# mano_rev_1_2_b.net
KiCad netlist of a schematic drawn in EAGLE
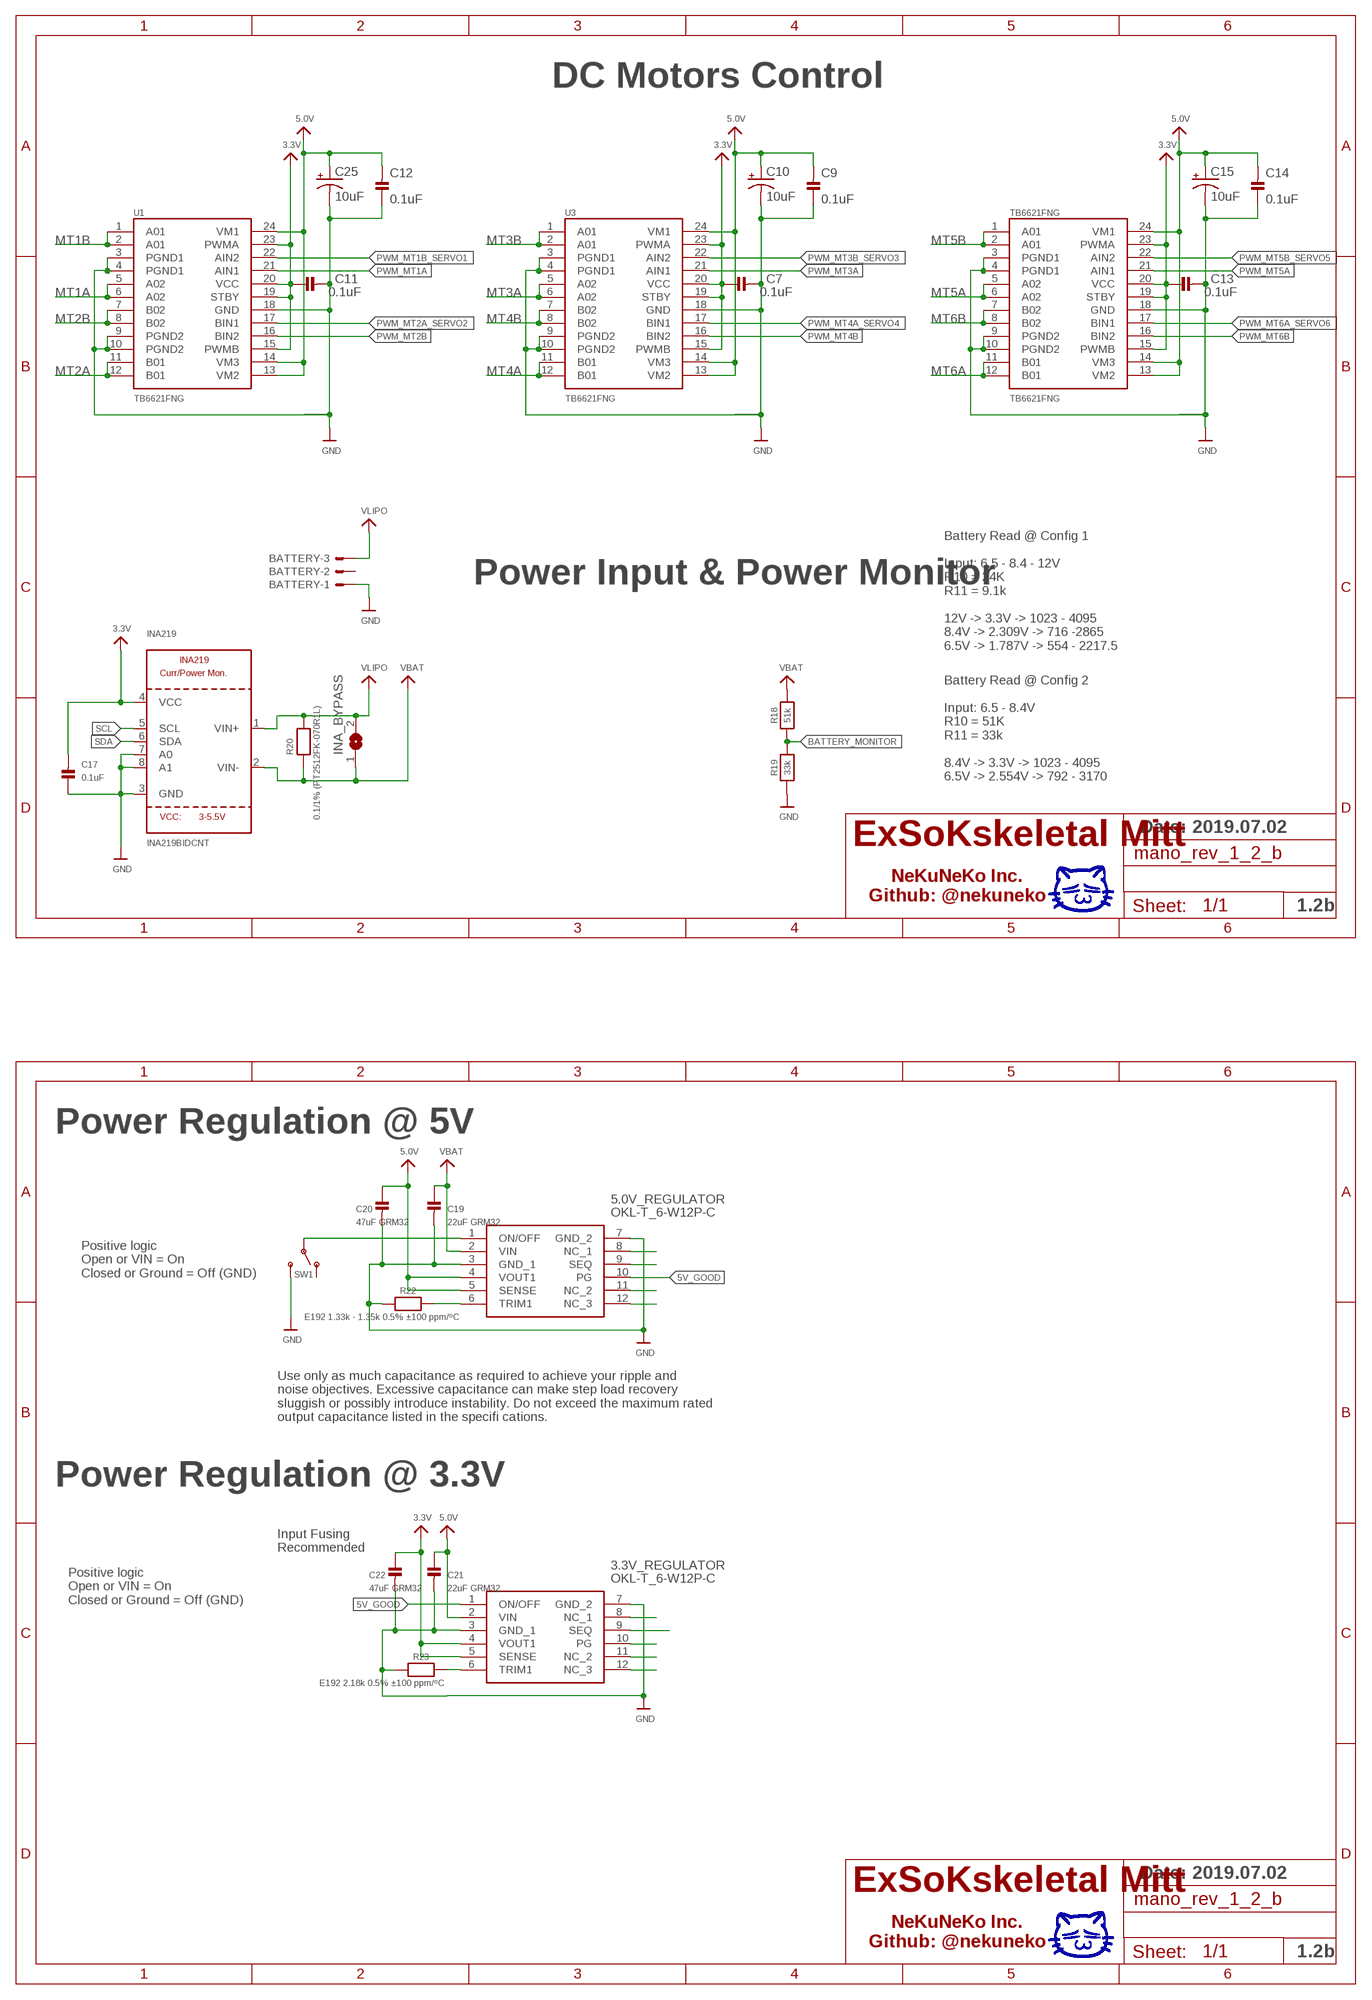
[diagram p0: schematic, sheet 1, part 1 of 2]
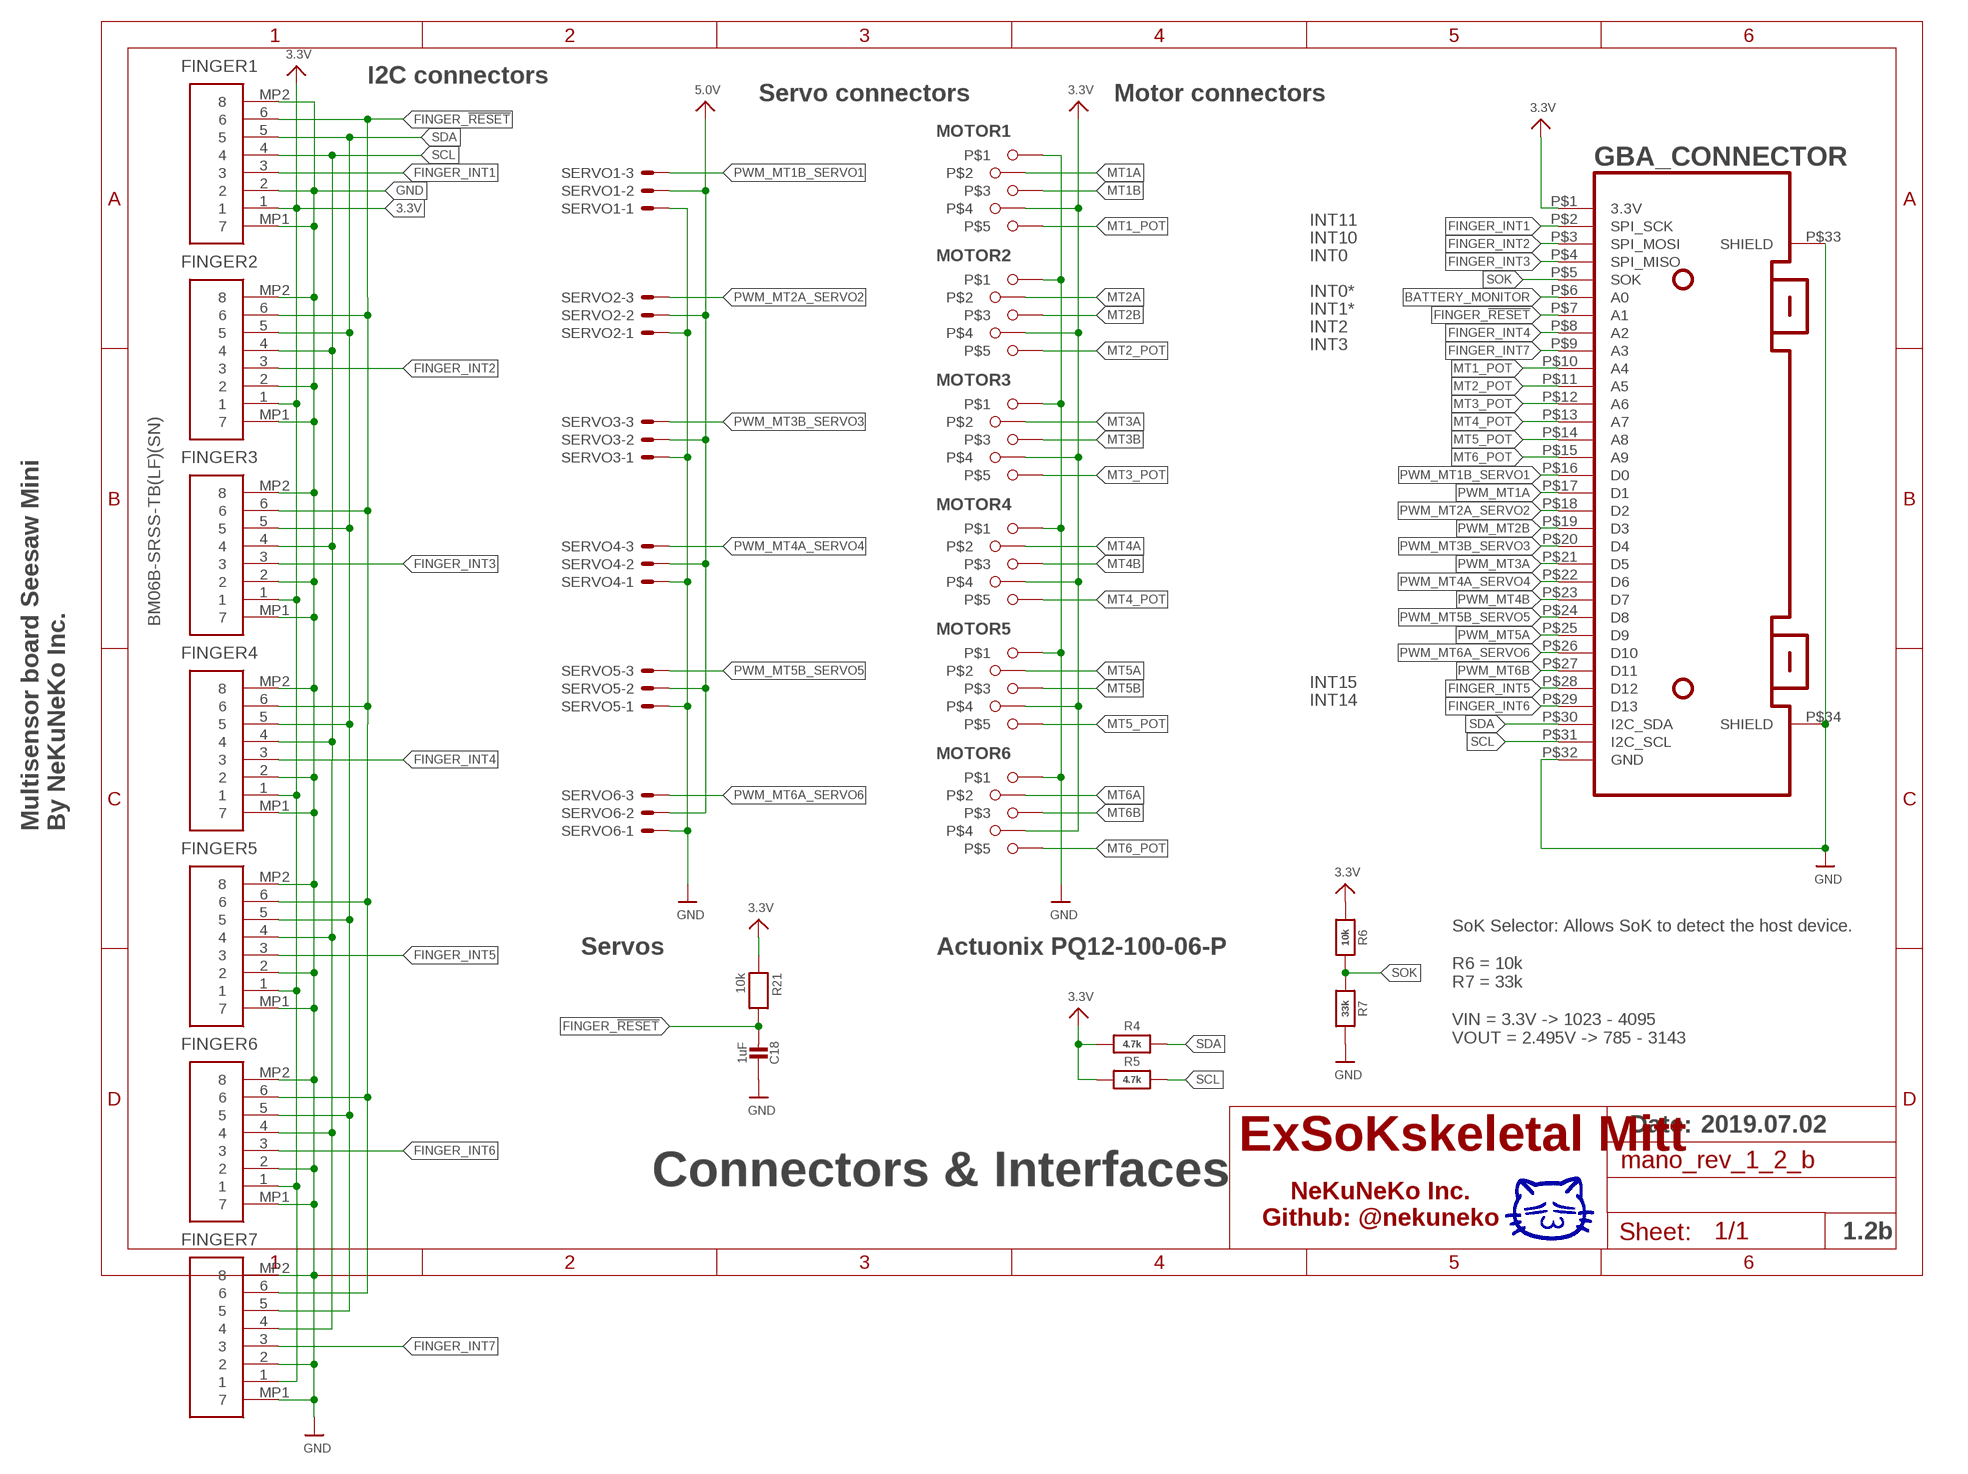
[diagram p1: schematic, sheet 1, part 2 of 2]

(export (version "E")
  (design (tool "Eeschema 10.0.6"))
  (components
    (comp (ref "3.3V_REGULATOR")
      (value "OKL-T_6-W12P-C")
      (footprint "eagle-import:OKL-T3-W12")
      (fields
        (field (name "MANUFACTURER_PART_NUMBER") "OKL-T/6-W12P-C")
        (field (name "MOUSER_PART_NUMBER") "580-OKL-T/6-W12P-C")
      )
      (libsource (lib "eagle-import") (part "OKL-T_6-W12P-C"))
    )
    (comp (ref "5.0V_REGULATOR")
      (value "OKL-T_6-W12P-C")
      (footprint "eagle-import:OKL-T3-W12")
      (fields
        (field (name "MANUFACTURER_PART_NUMBER") "OKL-T/6-W12P-C")
        (field (name "MOUSER_PART_NUMBER") "580-OKL-T/6-W12P-C")
      )
      (libsource (lib "eagle-import") (part "OKL-T_6-W12P-C"))
    )
    (comp (ref "BATTERY")
      (value "JST-XH-03-PIN-LONG-PAD")
      (footprint "eagle-import:JST-XH-03-PACKAGE-LONG-PAD")
      (libsource (lib "eagle-import") (part "JST-XH-03-PIN-LONG-PAD"))
    )
    (comp (ref "C7")
      (value "0.1uF")
      (footprint "eagle-import:_0603")
      (libsource (lib "eagle-import") (part "microbuilder_CAP_CERAMIC_0603"))
    )
    (comp (ref "C9")
      (value "0.1uF")
      (footprint "eagle-import:_0603")
      (libsource (lib "eagle-import") (part "microbuilder_CAP_CERAMIC_0603"))
    )
    (comp (ref "C10")
      (value "10uF")
      (footprint "eagle-import:0603-POLAR")
      (fields (field (name "MPN") "F981A106MMA"))
      (libsource (lib "eagle-import") (part "10UF-POLAR-0603-6.3V-20%(TANT)"))
    )
    (comp (ref "C11")
      (value "0.1uF")
      (footprint "eagle-import:_0603")
      (libsource (lib "eagle-import") (part "microbuilder_CAP_CERAMIC_0603"))
    )
    (comp (ref "C12")
      (value "0.1uF")
      (footprint "eagle-import:_0603")
      (libsource (lib "eagle-import") (part "microbuilder_CAP_CERAMIC_0603"))
    )
    (comp (ref "C13")
      (value "0.1uF")
      (footprint "eagle-import:_0603")
      (libsource (lib "eagle-import") (part "microbuilder_CAP_CERAMIC_0603"))
    )
    (comp (ref "C14")
      (value "0.1uF")
      (footprint "eagle-import:_0603")
      (libsource (lib "eagle-import") (part "microbuilder_CAP_CERAMIC_0603"))
    )
    (comp (ref "C15")
      (value "10uF")
      (footprint "eagle-import:0603-POLAR")
      (fields (field (name "MPN") "F981A106MMA"))
      (libsource (lib "eagle-import") (part "10UF-POLAR-0603-6.3V-20%(TANT)"))
    )
    (comp (ref "C17")
      (value "0.1uF")
      (footprint "eagle-import:_0603")
      (libsource (lib "eagle-import") (part "microbuilder_CAP_CERAMIC_0603"))
    )
    (comp (ref "C18")
      (value "1uF")
      (footprint "eagle-import:MICROBUILDER__0603")
      (libsource (lib "eagle-import") (part "CAP_CERAMIC_0603"))
    )
    (comp (ref "C19")
      (value "22uF GRM32")
      (footprint "eagle-import:1206")
      (libsource (lib "eagle-import") (part "CAP_CERAMIC1206"))
    )
    (comp (ref "C20")
      (value "47uF GRM32")
      (footprint "eagle-import:1206")
      (libsource (lib "eagle-import") (part "CAP_CERAMIC1206"))
    )
    (comp (ref "C21")
      (value "22uF GRM32")
      (footprint "eagle-import:1206")
      (libsource (lib "eagle-import") (part "CAP_CERAMIC1206"))
    )
    (comp (ref "C22")
      (value "47uF GRM32")
      (footprint "eagle-import:1206")
      (libsource (lib "eagle-import") (part "CAP_CERAMIC1206"))
    )
    (comp (ref "C25")
      (value "10uF")
      (footprint "eagle-import:0603-POLAR")
      (fields (field (name "MPN") "F981A106MMA"))
      (libsource (lib "eagle-import") (part "10UF-POLAR-0603-6.3V-20%(TANT)"))
    )
    (comp (ref "FINGER1")
      (value "BM06B-SRSS-TB(LF)(SN)")
      (footprint "eagle-import:BM06BSRSSTBLFSN")
      (fields (field (name "RS_PART_NUMBER") "5468782"))
      (libsource (lib "eagle-import") (part "BM06B-SRSS-TB(LF)(SN)"))
    )
    (comp (ref "FINGER2")
      (value "BM06B-SRSS-TB(LF)(SN)")
      (footprint "eagle-import:BM06BSRSSTBLFSN")
      (fields (field (name "RS_PART_NUMBER") "5468782"))
      (libsource (lib "eagle-import") (part "BM06B-SRSS-TB(LF)(SN)"))
    )
    (comp (ref "FINGER3")
      (value "BM06B-SRSS-TB(LF)(SN)")
      (footprint "eagle-import:BM06BSRSSTBLFSN")
      (fields (field (name "RS_PART_NUMBER") "5468782"))
      (libsource (lib "eagle-import") (part "BM06B-SRSS-TB(LF)(SN)"))
    )
    (comp (ref "FINGER4")
      (value "BM06B-SRSS-TB(LF)(SN)")
      (footprint "eagle-import:BM06BSRSSTBLFSN")
      (fields (field (name "RS_PART_NUMBER") "5468782"))
      (libsource (lib "eagle-import") (part "BM06B-SRSS-TB(LF)(SN)"))
    )
    (comp (ref "FINGER5")
      (value "BM06B-SRSS-TB(LF)(SN)")
      (footprint "eagle-import:BM06BSRSSTBLFSN")
      (fields (field (name "RS_PART_NUMBER") "5468782"))
      (libsource (lib "eagle-import") (part "BM06B-SRSS-TB(LF)(SN)"))
    )
    (comp (ref "FINGER6")
      (value "BM06B-SRSS-TB(LF)(SN)")
      (footprint "eagle-import:BM06BSRSSTBLFSN")
      (fields (field (name "RS_PART_NUMBER") "5468782"))
      (libsource (lib "eagle-import") (part "BM06B-SRSS-TB(LF)(SN)"))
    )
    (comp (ref "FINGER7")
      (value "BM06B-SRSS-TB(LF)(SN)")
      (footprint "eagle-import:BM06BSRSSTBLFSN")
      (fields (field (name "RS_PART_NUMBER") "5468782"))
      (libsource (lib "eagle-import") (part "BM06B-SRSS-TB(LF)(SN)"))
    )
    (comp (ref "GBA_CONNECTOR")
      (value "GBA_CARTRIDGEGBA_CARTRIDGE2")
      (footprint "eagle-import:GBA_CARTRIDGE2")
      (libsource (lib "eagle-import") (part "GBA_CARTRIDGEGBA_CARTRIDGE2"))
    )
    (comp (ref "INA219")
      (value "INA219BIDCNT")
      (footprint "eagle-import:SOT23-8")
      (libsource (lib "eagle-import") (part "INA219"))
    )
    (comp (ref "INA_BYPASS")
      (value "SOLDERJUMPERREFLOW_NOPASTE")
      (footprint "eagle-import:SOLDERJUMPER_REFLOW_NOPASTE")
      (libsource (lib "eagle-import") (part "SOLDERJUMPERREFLOW_NOPASTE"))
    )
    (comp (ref "MOTOR1")
      (value "Actuonix PQ12-100-06-P")
      (footprint "eagle-import:5PIN")
      (libsource (lib "eagle-import") (part "5PIN"))
    )
    (comp (ref "MOTOR2")
      (value "Actuonix PQ12-100-06-P")
      (footprint "eagle-import:5PIN")
      (libsource (lib "eagle-import") (part "5PIN"))
    )
    (comp (ref "MOTOR3")
      (value "Actuonix PQ12-100-06-P")
      (footprint "eagle-import:5PIN")
      (libsource (lib "eagle-import") (part "5PIN"))
    )
    (comp (ref "MOTOR4")
      (value "Actuonix PQ12-100-06-P")
      (footprint "eagle-import:5PIN")
      (libsource (lib "eagle-import") (part "5PIN"))
    )
    (comp (ref "MOTOR5")
      (value "Actuonix PQ12-100-06-P")
      (footprint "eagle-import:5PIN")
      (libsource (lib "eagle-import") (part "5PIN"))
    )
    (comp (ref "MOTOR6")
      (value "Actuonix PQ12-100-06-P")
      (footprint "eagle-import:5PIN")
      (libsource (lib "eagle-import") (part "5PIN"))
    )
    (comp (ref "R4")
      (value "4.7k")
      (footprint "eagle-import:_0603")
      (libsource (lib "eagle-import") (part "RESISTOR_0603"))
    )
    (comp (ref "R5")
      (value "4.7k")
      (footprint "eagle-import:_0603")
      (libsource (lib "eagle-import") (part "RESISTOR_0603"))
    )
    (comp (ref "R6")
      (value "10k")
      (footprint "eagle-import:_0603")
      (libsource (lib "eagle-import") (part "RESISTOR_0603"))
    )
    (comp (ref "R7")
      (value "33k")
      (footprint "eagle-import:_0603")
      (libsource (lib "eagle-import") (part "RESISTOR_0603"))
    )
    (comp (ref "R18")
      (value "51k")
      (footprint "eagle-import:_0603")
      (libsource (lib "eagle-import") (part "RESISTOR_0603"))
    )
    (comp (ref "R19")
      (value "33k")
      (footprint "eagle-import:_0603")
      (libsource (lib "eagle-import") (part "RESISTOR_0603"))
    )
    (comp (ref "R20")
      (value "0.1/1% (PT2512FK-070R1L)")
      (footprint "eagle-import:2512")
      (libsource (lib "eagle-import") (part "RESISTOR2512"))
    )
    (comp (ref "R21")
      (value "10k")
      (footprint "eagle-import:_0603")
      (libsource (lib "eagle-import") (part "RESISTOR_0603"))
    )
    (comp (ref "R22")
      (value "E192 1.33k - 1.35k 0.5% ±100 ppm/ºC")
      (footprint "eagle-import:_0603")
      (libsource (lib "eagle-import") (part "RESISTOR_0603"))
    )
    (comp (ref "R23")
      (value "E192 2.18k 0.5% ±100 ppm/ºC")
      (footprint "eagle-import:_0603")
      (libsource (lib "eagle-import") (part "RESISTOR_0603"))
    )
    (comp (ref "SERVO1")
      (value "JST-XH-03-PIN-LONG-PAD")
      (footprint "eagle-import:JST-XH-03-PACKAGE-LONG-PAD")
      (libsource (lib "eagle-import") (part "JST-XH-03-PIN-LONG-PAD"))
    )
    (comp (ref "SERVO2")
      (value "JST-XH-03-PIN-LONG-PAD")
      (footprint "eagle-import:JST-XH-03-PACKAGE-LONG-PAD")
      (libsource (lib "eagle-import") (part "JST-XH-03-PIN-LONG-PAD"))
    )
    (comp (ref "SERVO3")
      (value "JST-XH-03-PIN-LONG-PAD")
      (footprint "eagle-import:JST-XH-03-PACKAGE-LONG-PAD")
      (libsource (lib "eagle-import") (part "JST-XH-03-PIN-LONG-PAD"))
    )
    (comp (ref "SERVO4")
      (value "JST-XH-03-PIN-LONG-PAD")
      (footprint "eagle-import:JST-XH-03-PACKAGE-LONG-PAD")
      (libsource (lib "eagle-import") (part "JST-XH-03-PIN-LONG-PAD"))
    )
    (comp (ref "SERVO5")
      (value "JST-XH-03-PIN-LONG-PAD")
      (footprint "eagle-import:JST-XH-03-PACKAGE-LONG-PAD")
      (libsource (lib "eagle-import") (part "JST-XH-03-PIN-LONG-PAD"))
    )
    (comp (ref "SERVO6")
      (value "JST-XH-03-PIN-LONG-PAD")
      (footprint "eagle-import:JST-XH-03-PACKAGE-LONG-PAD")
      (libsource (lib "eagle-import") (part "JST-XH-03-PIN-LONG-PAD"))
    )
    (comp (ref "SW1")
      (value "SWITCH_SPDT")
      (footprint "eagle-import:SPDT_SMT_SSSS811101")
      (libsource (lib "eagle-import") (part "SWITCH_SPDT"))
    )
    (comp (ref "TB6621FNG")
      (value "TB6621FNG")
      (footprint "eagle-import:SSOP24")
      (libsource (lib "eagle-import") (part "TB6621FNG"))
    )
    (comp (ref "U1")
      (value "TB6621FNG")
      (footprint "eagle-import:SSOP24")
      (libsource (lib "eagle-import") (part "TB6621FNG"))
    )
    (comp (ref "U3")
      (value "TB6621FNG")
      (footprint "eagle-import:SSOP24")
      (libsource (lib "eagle-import") (part "TB6621FNG"))
    )
  )
  (nets
    (net (code "1") (name "/FINGER_~{RESET}") (class "Default")
      (node (ref "C18") (pin "2") (pinfunction "2_2") (pintype "passive"))
      (node (ref "FINGER1") (pin "6") (pinfunction "6_6") (pintype "bidirectional"))
      (node (ref "FINGER2") (pin "6") (pinfunction "6_6") (pintype "bidirectional"))
      (node (ref "FINGER3") (pin "6") (pinfunction "6_6") (pintype "bidirectional"))
      (node (ref "FINGER4") (pin "6") (pinfunction "6_6") (pintype "bidirectional"))
      (node (ref "FINGER5") (pin "6") (pinfunction "6_6") (pintype "bidirectional"))
      (node (ref "FINGER6") (pin "6") (pinfunction "6_6") (pintype "bidirectional"))
      (node (ref "FINGER7") (pin "6") (pinfunction "6_6") (pintype "bidirectional"))
      (node (ref "GBA_CONNECTOR") (pin "P$7") (pinfunction "A1_P$7") (pintype "bidirectional"))
      (node (ref "R21") (pin "2") (pinfunction "2_2") (pintype "passive"))
    )
    (net (code "2") (name "3.3V") (class "Default")
      (node (ref "3.3V_REGULATOR") (pin "4") (pinfunction "VOUT1_4") (pintype "bidirectional"))
      (node (ref "3.3V_REGULATOR") (pin "5") (pinfunction "SENSE_5") (pintype "bidirectional"))
      (node (ref "C11") (pin "1") (pinfunction "P$1_1") (pintype "passive"))
      (node (ref "C13") (pin "1") (pinfunction "P$1_1") (pintype "passive"))
      (node (ref "C17") (pin "2") (pinfunction "P$2_2") (pintype "passive"))
      (node (ref "C22") (pin "1") (pinfunction "P$1_1") (pintype "passive"))
      (node (ref "C7") (pin "1") (pinfunction "P$1_1") (pintype "passive"))
      (node (ref "FINGER1") (pin "1") (pinfunction "1_1") (pintype "bidirectional"))
      (node (ref "FINGER2") (pin "1") (pinfunction "1_1") (pintype "bidirectional"))
      (node (ref "FINGER3") (pin "1") (pinfunction "1_1") (pintype "bidirectional"))
      (node (ref "FINGER4") (pin "1") (pinfunction "1_1") (pintype "bidirectional"))
      (node (ref "FINGER5") (pin "1") (pinfunction "1_1") (pintype "bidirectional"))
      (node (ref "FINGER6") (pin "1") (pinfunction "1_1") (pintype "bidirectional"))
      (node (ref "FINGER7") (pin "1") (pinfunction "1_1") (pintype "bidirectional"))
      (node (ref "GBA_CONNECTOR") (pin "P$1") (pinfunction "3.3V_P$1") (pintype "power_in"))
      (node (ref "INA219") (pin "4") (pinfunction "VCC_4") (pintype "bidirectional"))
      (node (ref "MOTOR1") (pin "4") (pinfunction "P$4_4") (pintype "bidirectional"))
      (node (ref "MOTOR2") (pin "4") (pinfunction "P$4_4") (pintype "bidirectional"))
      (node (ref "MOTOR3") (pin "4") (pinfunction "P$4_4") (pintype "bidirectional"))
      (node (ref "MOTOR4") (pin "4") (pinfunction "P$4_4") (pintype "bidirectional"))
      (node (ref "MOTOR5") (pin "4") (pinfunction "P$4_4") (pintype "bidirectional"))
      (node (ref "MOTOR6") (pin "4") (pinfunction "P$4_4") (pintype "bidirectional"))
      (node (ref "R21") (pin "1") (pinfunction "1_1") (pintype "passive"))
      (node (ref "R4") (pin "1") (pinfunction "1_1") (pintype "passive"))
      (node (ref "R5") (pin "1") (pinfunction "1_1") (pintype "passive"))
      (node (ref "R6") (pin "1") (pinfunction "1_1") (pintype "passive"))
      (node (ref "TB6621FNG") (pin "15") (pinfunction "PWMB_15") (pintype "bidirectional"))
      (node (ref "TB6621FNG") (pin "19") (pinfunction "STBY_19") (pintype "bidirectional"))
      (node (ref "TB6621FNG") (pin "20") (pinfunction "VCC_20") (pintype "bidirectional"))
      (node (ref "TB6621FNG") (pin "23") (pinfunction "PWMA_23") (pintype "bidirectional"))
      (node (ref "U1") (pin "15") (pinfunction "PWMB_15") (pintype "bidirectional"))
      (node (ref "U1") (pin "19") (pinfunction "STBY_19") (pintype "bidirectional"))
      (node (ref "U1") (pin "20") (pinfunction "VCC_20") (pintype "bidirectional"))
      (node (ref "U1") (pin "23") (pinfunction "PWMA_23") (pintype "bidirectional"))
      (node (ref "U3") (pin "15") (pinfunction "PWMB_15") (pintype "bidirectional"))
      (node (ref "U3") (pin "19") (pinfunction "STBY_19") (pintype "bidirectional"))
      (node (ref "U3") (pin "20") (pinfunction "VCC_20") (pintype "bidirectional"))
      (node (ref "U3") (pin "23") (pinfunction "PWMA_23") (pintype "bidirectional"))
    )
    (net (code "3") (name "5.0V") (class "Default")
      (node (ref "3.3V_REGULATOR") (pin "2") (pinfunction "VIN_2") (pintype "bidirectional"))
      (node (ref "5.0V_REGULATOR") (pin "4") (pinfunction "VOUT1_4") (pintype "bidirectional"))
      (node (ref "5.0V_REGULATOR") (pin "5") (pinfunction "SENSE_5") (pintype "bidirectional"))
      (node (ref "C10") (pin "+") (pinfunction "+_+") (pintype "passive"))
      (node (ref "C12") (pin "2") (pinfunction "P$2_2") (pintype "passive"))
      (node (ref "C14") (pin "2") (pinfunction "P$2_2") (pintype "passive"))
      (node (ref "C15") (pin "+") (pinfunction "+_+") (pintype "passive"))
      (node (ref "C20") (pin "1") (pinfunction "P$1_1") (pintype "passive"))
      (node (ref "C21") (pin "1") (pinfunction "P$1_1") (pintype "passive"))
      (node (ref "C25") (pin "+") (pinfunction "+_+") (pintype "passive"))
      (node (ref "C9") (pin "2") (pinfunction "P$2_2") (pintype "passive"))
      (node (ref "SERVO1") (pin "2") (pinfunction "S_2") (pintype "passive"))
      (node (ref "SERVO2") (pin "2") (pinfunction "S_2") (pintype "passive"))
      (node (ref "SERVO3") (pin "2") (pinfunction "S_2") (pintype "passive"))
      (node (ref "SERVO4") (pin "2") (pinfunction "S_2") (pintype "passive"))
      (node (ref "SERVO5") (pin "2") (pinfunction "S_2") (pintype "passive"))
      (node (ref "SERVO6") (pin "2") (pinfunction "S_2") (pintype "passive"))
      (node (ref "TB6621FNG") (pin "13") (pinfunction "VM2_13") (pintype "bidirectional"))
      (node (ref "TB6621FNG") (pin "14") (pinfunction "VM3_14") (pintype "bidirectional"))
      (node (ref "TB6621FNG") (pin "24") (pinfunction "VM1_24") (pintype "bidirectional"))
      (node (ref "U1") (pin "13") (pinfunction "VM2_13") (pintype "bidirectional"))
      (node (ref "U1") (pin "14") (pinfunction "VM3_14") (pintype "bidirectional"))
      (node (ref "U1") (pin "24") (pinfunction "VM1_24") (pintype "bidirectional"))
      (node (ref "U3") (pin "13") (pinfunction "VM2_13") (pintype "bidirectional"))
      (node (ref "U3") (pin "14") (pinfunction "VM3_14") (pintype "bidirectional"))
      (node (ref "U3") (pin "24") (pinfunction "VM1_24") (pintype "bidirectional"))
    )
    (net (code "4") (name "5V_GOOD") (class "Default")
      (node (ref "3.3V_REGULATOR") (pin "1") (pinfunction "ON/OFF_1") (pintype "bidirectional"))
      (node (ref "5.0V_REGULATOR") (pin "10") (pinfunction "PG_10") (pintype "bidirectional"))
    )
    (net (code "5") (name "BATTERY_MONITOR") (class "Default")
      (node (ref "GBA_CONNECTOR") (pin "P$6") (pinfunction "A0_P$6") (pintype "bidirectional"))
      (node (ref "R18") (pin "1") (pinfunction "1_1") (pintype "passive"))
      (node (ref "R19") (pin "2") (pinfunction "2_2") (pintype "passive"))
    )
    (net (code "6") (name "FINGER_INT1") (class "Default")
      (node (ref "FINGER1") (pin "3") (pinfunction "3_3") (pintype "bidirectional"))
      (node (ref "GBA_CONNECTOR") (pin "P$2") (pinfunction "SPI_SCK_P$2") (pintype "bidirectional"))
    )
    (net (code "7") (name "FINGER_INT2") (class "Default")
      (node (ref "FINGER2") (pin "3") (pinfunction "3_3") (pintype "bidirectional"))
      (node (ref "GBA_CONNECTOR") (pin "P$3") (pinfunction "SPI_MOSI_P$3") (pintype "bidirectional"))
    )
    (net (code "8") (name "FINGER_INT3") (class "Default")
      (node (ref "FINGER3") (pin "3") (pinfunction "3_3") (pintype "bidirectional"))
      (node (ref "GBA_CONNECTOR") (pin "P$4") (pinfunction "SPI_MISO_P$4") (pintype "bidirectional"))
    )
    (net (code "9") (name "FINGER_INT4") (class "Default")
      (node (ref "FINGER4") (pin "3") (pinfunction "3_3") (pintype "bidirectional"))
      (node (ref "GBA_CONNECTOR") (pin "P$8") (pinfunction "A2_P$8") (pintype "bidirectional"))
    )
    (net (code "10") (name "FINGER_INT5") (class "Default")
      (node (ref "FINGER5") (pin "3") (pinfunction "3_3") (pintype "bidirectional"))
      (node (ref "GBA_CONNECTOR") (pin "P$28") (pinfunction "D12_P$28") (pintype "bidirectional"))
    )
    (net (code "11") (name "FINGER_INT6") (class "Default")
      (node (ref "FINGER6") (pin "3") (pinfunction "3_3") (pintype "bidirectional"))
      (node (ref "GBA_CONNECTOR") (pin "P$29") (pinfunction "D13_P$29") (pintype "bidirectional"))
    )
    (net (code "12") (name "FINGER_INT7") (class "Default")
      (node (ref "FINGER7") (pin "3") (pinfunction "3_3") (pintype "bidirectional"))
      (node (ref "GBA_CONNECTOR") (pin "P$9") (pinfunction "A3_P$9") (pintype "bidirectional"))
    )
    (net (code "13") (name "GND") (class "Default")
      (node (ref "3.3V_REGULATOR") (pin "3") (pinfunction "GND_1_3") (pintype "bidirectional"))
      (node (ref "3.3V_REGULATOR") (pin "7") (pinfunction "GND_2_7") (pintype "bidirectional"))
      (node (ref "5.0V_REGULATOR") (pin "3") (pinfunction "GND_1_3") (pintype "bidirectional"))
      (node (ref "5.0V_REGULATOR") (pin "7") (pinfunction "GND_2_7") (pintype "bidirectional"))
      (node (ref "BATTERY") (pin "1") (pinfunction "S_1") (pintype "passive"))
      (node (ref "C10") (pin "-") (pinfunction "-_-") (pintype "passive"))
      (node (ref "C11") (pin "2") (pinfunction "P$2_2") (pintype "passive"))
      (node (ref "C12") (pin "1") (pinfunction "P$1_1") (pintype "passive"))
      (node (ref "C13") (pin "2") (pinfunction "P$2_2") (pintype "passive"))
      (node (ref "C14") (pin "1") (pinfunction "P$1_1") (pintype "passive"))
      (node (ref "C15") (pin "-") (pinfunction "-_-") (pintype "passive"))
      (node (ref "C17") (pin "1") (pinfunction "P$1_1") (pintype "passive"))
      (node (ref "C18") (pin "1") (pinfunction "1_1") (pintype "passive"))
      (node (ref "C19") (pin "2") (pinfunction "P$2_2") (pintype "passive"))
      (node (ref "C20") (pin "2") (pinfunction "P$2_2") (pintype "passive"))
      (node (ref "C21") (pin "2") (pinfunction "P$2_2") (pintype "passive"))
      (node (ref "C22") (pin "2") (pinfunction "P$2_2") (pintype "passive"))
      (node (ref "C25") (pin "-") (pinfunction "-_-") (pintype "passive"))
      (node (ref "C7") (pin "2") (pinfunction "P$2_2") (pintype "passive"))
      (node (ref "C9") (pin "1") (pinfunction "P$1_1") (pintype "passive"))
      (node (ref "FINGER1") (pin "2") (pinfunction "2_2") (pintype "bidirectional"))
      (node (ref "FINGER1") (pin "MP1") (pinfunction "7_MP1") (pintype "bidirectional"))
      (node (ref "FINGER1") (pin "MP2") (pinfunction "8_MP2") (pintype "bidirectional"))
      (node (ref "FINGER2") (pin "2") (pinfunction "2_2") (pintype "bidirectional"))
      (node (ref "FINGER2") (pin "MP1") (pinfunction "7_MP1") (pintype "bidirectional"))
      (node (ref "FINGER2") (pin "MP2") (pinfunction "8_MP2") (pintype "bidirectional"))
      (node (ref "FINGER3") (pin "2") (pinfunction "2_2") (pintype "bidirectional"))
      (node (ref "FINGER3") (pin "MP1") (pinfunction "7_MP1") (pintype "bidirectional"))
      (node (ref "FINGER3") (pin "MP2") (pinfunction "8_MP2") (pintype "bidirectional"))
      (node (ref "FINGER4") (pin "2") (pinfunction "2_2") (pintype "bidirectional"))
      (node (ref "FINGER4") (pin "MP1") (pinfunction "7_MP1") (pintype "bidirectional"))
      (node (ref "FINGER4") (pin "MP2") (pinfunction "8_MP2") (pintype "bidirectional"))
      (node (ref "FINGER5") (pin "2") (pinfunction "2_2") (pintype "bidirectional"))
      (node (ref "FINGER5") (pin "MP1") (pinfunction "7_MP1") (pintype "bidirectional"))
      (node (ref "FINGER5") (pin "MP2") (pinfunction "8_MP2") (pintype "bidirectional"))
      (node (ref "FINGER6") (pin "2") (pinfunction "2_2") (pintype "bidirectional"))
      (node (ref "FINGER6") (pin "MP1") (pinfunction "7_MP1") (pintype "bidirectional"))
      (node (ref "FINGER6") (pin "MP2") (pinfunction "8_MP2") (pintype "bidirectional"))
      (node (ref "FINGER7") (pin "2") (pinfunction "2_2") (pintype "bidirectional"))
      (node (ref "FINGER7") (pin "MP1") (pinfunction "7_MP1") (pintype "bidirectional"))
      (node (ref "FINGER7") (pin "MP2") (pinfunction "8_MP2") (pintype "bidirectional"))
      (node (ref "GBA_CONNECTOR") (pin "P$32") (pinfunction "GND_P$32") (pintype "power_in"))
      (node (ref "GBA_CONNECTOR") (pin "P$33") (pinfunction "SHIELD_P$33") (pintype "bidirectional"))
      (node (ref "GBA_CONNECTOR") (pin "P$34") (pinfunction "SHIELD_P$34") (pintype "bidirectional"))
      (node (ref "INA219") (pin "3") (pinfunction "GND_3") (pintype "bidirectional"))
      (node (ref "INA219") (pin "7") (pinfunction "A0_7") (pintype "bidirectional"))
      (node (ref "INA219") (pin "8") (pinfunction "A1_8") (pintype "bidirectional"))
      (node (ref "MOTOR1") (pin "1") (pinfunction "P$1_1") (pintype "bidirectional"))
      (node (ref "MOTOR2") (pin "1") (pinfunction "P$1_1") (pintype "bidirectional"))
      (node (ref "MOTOR3") (pin "1") (pinfunction "P$1_1") (pintype "bidirectional"))
      (node (ref "MOTOR4") (pin "1") (pinfunction "P$1_1") (pintype "bidirectional"))
      (node (ref "MOTOR5") (pin "1") (pinfunction "P$1_1") (pintype "bidirectional"))
      (node (ref "MOTOR6") (pin "1") (pinfunction "P$1_1") (pintype "bidirectional"))
      (node (ref "R19") (pin "1") (pinfunction "1_1") (pintype "passive"))
      (node (ref "R22") (pin "2") (pinfunction "2_2") (pintype "passive"))
      (node (ref "R23") (pin "2") (pinfunction "2_2") (pintype "passive"))
      (node (ref "R7") (pin "2") (pinfunction "2_2") (pintype "passive"))
      (node (ref "SERVO1") (pin "1") (pinfunction "S_1") (pintype "passive"))
      (node (ref "SERVO2") (pin "1") (pinfunction "S_1") (pintype "passive"))
      (node (ref "SERVO3") (pin "1") (pinfunction "S_1") (pintype "passive"))
      (node (ref "SERVO4") (pin "1") (pinfunction "S_1") (pintype "passive"))
      (node (ref "SERVO5") (pin "1") (pinfunction "S_1") (pintype "passive"))
      (node (ref "SERVO6") (pin "1") (pinfunction "S_1") (pintype "passive"))
      (node (ref "SW1") (pin "C") (pinfunction "S_C") (pintype "passive"))
      (node (ref "TB6621FNG") (pin "10") (pinfunction "PGND2_10") (pintype "bidirectional"))
      (node (ref "TB6621FNG") (pin "18") (pinfunction "GND_18") (pintype "bidirectional"))
      (node (ref "TB6621FNG") (pin "3") (pinfunction "PGND1_3") (pintype "bidirectional"))
      (node (ref "TB6621FNG") (pin "4") (pinfunction "PGND1_4") (pintype "bidirectional"))
      (node (ref "TB6621FNG") (pin "9") (pinfunction "PGND2_9") (pintype "bidirectional"))
      (node (ref "U1") (pin "10") (pinfunction "PGND2_10") (pintype "bidirectional"))
      (node (ref "U1") (pin "18") (pinfunction "GND_18") (pintype "bidirectional"))
      (node (ref "U1") (pin "3") (pinfunction "PGND1_3") (pintype "bidirectional"))
      (node (ref "U1") (pin "4") (pinfunction "PGND1_4") (pintype "bidirectional"))
      (node (ref "U1") (pin "9") (pinfunction "PGND2_9") (pintype "bidirectional"))
      (node (ref "U3") (pin "10") (pinfunction "PGND2_10") (pintype "bidirectional"))
      (node (ref "U3") (pin "18") (pinfunction "GND_18") (pintype "bidirectional"))
      (node (ref "U3") (pin "3") (pinfunction "PGND1_3") (pintype "bidirectional"))
      (node (ref "U3") (pin "4") (pinfunction "PGND1_4") (pintype "bidirectional"))
      (node (ref "U3") (pin "9") (pinfunction "PGND2_9") (pintype "bidirectional"))
    )
    (net (code "14") (name "MT1A") (class "Default")
      (node (ref "MOTOR1") (pin "2") (pinfunction "P$2_2") (pintype "bidirectional"))
      (node (ref "U1") (pin "5") (pinfunction "A02_5") (pintype "bidirectional"))
      (node (ref "U1") (pin "6") (pinfunction "A02_6") (pintype "bidirectional"))
    )
    (net (code "15") (name "MT1B") (class "Default")
      (node (ref "MOTOR1") (pin "3") (pinfunction "P$3_3") (pintype "bidirectional"))
      (node (ref "U1") (pin "1") (pinfunction "A01_1") (pintype "bidirectional"))
      (node (ref "U1") (pin "2") (pinfunction "A01_2") (pintype "bidirectional"))
    )
    (net (code "16") (name "MT1_POT") (class "Default")
      (node (ref "GBA_CONNECTOR") (pin "P$10") (pinfunction "A4_P$10") (pintype "bidirectional"))
      (node (ref "MOTOR1") (pin "5") (pinfunction "P$5_5") (pintype "bidirectional"))
    )
    (net (code "17") (name "MT2A") (class "Default")
      (node (ref "MOTOR2") (pin "2") (pinfunction "P$2_2") (pintype "bidirectional"))
      (node (ref "U1") (pin "11") (pinfunction "B01_11") (pintype "bidirectional"))
      (node (ref "U1") (pin "12") (pinfunction "B01_12") (pintype "bidirectional"))
    )
    (net (code "18") (name "MT2B") (class "Default")
      (node (ref "MOTOR2") (pin "3") (pinfunction "P$3_3") (pintype "bidirectional"))
      (node (ref "U1") (pin "7") (pinfunction "B02_7") (pintype "bidirectional"))
      (node (ref "U1") (pin "8") (pinfunction "B02_8") (pintype "bidirectional"))
    )
    (net (code "19") (name "MT2_POT") (class "Default")
      (node (ref "GBA_CONNECTOR") (pin "P$11") (pinfunction "A5_P$11") (pintype "bidirectional"))
      (node (ref "MOTOR2") (pin "5") (pinfunction "P$5_5") (pintype "bidirectional"))
    )
    (net (code "20") (name "MT3A") (class "Default")
      (node (ref "MOTOR3") (pin "2") (pinfunction "P$2_2") (pintype "bidirectional"))
      (node (ref "U3") (pin "5") (pinfunction "A02_5") (pintype "bidirectional"))
      (node (ref "U3") (pin "6") (pinfunction "A02_6") (pintype "bidirectional"))
    )
    (net (code "21") (name "MT3B") (class "Default")
      (node (ref "MOTOR3") (pin "3") (pinfunction "P$3_3") (pintype "bidirectional"))
      (node (ref "U3") (pin "1") (pinfunction "A01_1") (pintype "bidirectional"))
      (node (ref "U3") (pin "2") (pinfunction "A01_2") (pintype "bidirectional"))
    )
    (net (code "22") (name "MT3_POT") (class "Default")
      (node (ref "GBA_CONNECTOR") (pin "P$12") (pinfunction "A6_P$12") (pintype "bidirectional"))
      (node (ref "MOTOR3") (pin "5") (pinfunction "P$5_5") (pintype "bidirectional"))
    )
    (net (code "23") (name "MT4A") (class "Default")
      (node (ref "MOTOR4") (pin "2") (pinfunction "P$2_2") (pintype "bidirectional"))
      (node (ref "U3") (pin "11") (pinfunction "B01_11") (pintype "bidirectional"))
      (node (ref "U3") (pin "12") (pinfunction "B01_12") (pintype "bidirectional"))
    )
    (net (code "24") (name "MT4B") (class "Default")
      (node (ref "MOTOR4") (pin "3") (pinfunction "P$3_3") (pintype "bidirectional"))
      (node (ref "U3") (pin "7") (pinfunction "B02_7") (pintype "bidirectional"))
      (node (ref "U3") (pin "8") (pinfunction "B02_8") (pintype "bidirectional"))
    )
    (net (code "25") (name "MT4_POT") (class "Default")
      (node (ref "GBA_CONNECTOR") (pin "P$13") (pinfunction "A7_P$13") (pintype "bidirectional"))
      (node (ref "MOTOR4") (pin "5") (pinfunction "P$5_5") (pintype "bidirectional"))
    )
    (net (code "26") (name "MT5A") (class "Default")
      (node (ref "MOTOR5") (pin "2") (pinfunction "P$2_2") (pintype "bidirectional"))
      (node (ref "TB6621FNG") (pin "5") (pinfunction "A02_5") (pintype "bidirectional"))
      (node (ref "TB6621FNG") (pin "6") (pinfunction "A02_6") (pintype "bidirectional"))
    )
    (net (code "27") (name "MT5B") (class "Default")
      (node (ref "MOTOR5") (pin "3") (pinfunction "P$3_3") (pintype "bidirectional"))
      (node (ref "TB6621FNG") (pin "1") (pinfunction "A01_1") (pintype "bidirectional"))
      (node (ref "TB6621FNG") (pin "2") (pinfunction "A01_2") (pintype "bidirectional"))
    )
    (net (code "28") (name "MT5_POT") (class "Default")
      (node (ref "GBA_CONNECTOR") (pin "P$14") (pinfunction "A8_P$14") (pintype "bidirectional"))
      (node (ref "MOTOR5") (pin "5") (pinfunction "P$5_5") (pintype "bidirectional"))
    )
    (net (code "29") (name "MT6A") (class "Default")
      (node (ref "MOTOR6") (pin "2") (pinfunction "P$2_2") (pintype "bidirectional"))
      (node (ref "TB6621FNG") (pin "11") (pinfunction "B01_11") (pintype "bidirectional"))
      (node (ref "TB6621FNG") (pin "12") (pinfunction "B01_12") (pintype "bidirectional"))
    )
    (net (code "30") (name "MT6B") (class "Default")
      (node (ref "MOTOR6") (pin "3") (pinfunction "P$3_3") (pintype "bidirectional"))
      (node (ref "TB6621FNG") (pin "7") (pinfunction "B02_7") (pintype "bidirectional"))
      (node (ref "TB6621FNG") (pin "8") (pinfunction "B02_8") (pintype "bidirectional"))
    )
    (net (code "31") (name "MT6_POT") (class "Default")
      (node (ref "GBA_CONNECTOR") (pin "P$15") (pinfunction "A9_P$15") (pintype "bidirectional"))
      (node (ref "MOTOR6") (pin "5") (pinfunction "P$5_5") (pintype "bidirectional"))
    )
    (net (code "32") (name "Net-(3.3V_REGULATOR-TRIM1)") (class "Default")
      (node (ref "3.3V_REGULATOR") (pin "6") (pinfunction "TRIM1_6") (pintype "bidirectional"))
      (node (ref "R23") (pin "1") (pinfunction "1_1") (pintype "passive"))
    )
    (net (code "33") (name "Net-(5.0V_REGULATOR-ON{slash}OFF)") (class "Default")
      (node (ref "5.0V_REGULATOR") (pin "1") (pinfunction "ON/OFF_1") (pintype "bidirectional"))
      (node (ref "SW1") (pin "B") (pinfunction "P_B") (pintype "passive"))
    )
    (net (code "34") (name "Net-(5.0V_REGULATOR-TRIM1)") (class "Default")
      (node (ref "5.0V_REGULATOR") (pin "6") (pinfunction "TRIM1_6") (pintype "bidirectional"))
      (node (ref "R22") (pin "1") (pinfunction "1_1") (pintype "passive"))
    )
    (net (code "35") (name "PWM_MT1A") (class "Default")
      (node (ref "GBA_CONNECTOR") (pin "P$17") (pinfunction "D1_P$17") (pintype "bidirectional"))
      (node (ref "U1") (pin "21") (pinfunction "AIN1_21") (pintype "bidirectional"))
    )
    (net (code "36") (name "PWM_MT1B_SERVO1") (class "Default")
      (node (ref "GBA_CONNECTOR") (pin "P$16") (pinfunction "D0_P$16") (pintype "bidirectional"))
      (node (ref "SERVO1") (pin "3") (pinfunction "S_3") (pintype "passive"))
      (node (ref "U1") (pin "22") (pinfunction "AIN2_22") (pintype "bidirectional"))
    )
    (net (code "37") (name "PWM_MT2A_SERVO2") (class "Default")
      (node (ref "GBA_CONNECTOR") (pin "P$18") (pinfunction "D2_P$18") (pintype "bidirectional"))
      (node (ref "SERVO2") (pin "3") (pinfunction "S_3") (pintype "passive"))
      (node (ref "U1") (pin "17") (pinfunction "BIN1_17") (pintype "bidirectional"))
    )
    (net (code "38") (name "PWM_MT2B") (class "Default")
      (node (ref "GBA_CONNECTOR") (pin "P$19") (pinfunction "D3_P$19") (pintype "bidirectional"))
      (node (ref "U1") (pin "16") (pinfunction "BIN2_16") (pintype "bidirectional"))
    )
    (net (code "39") (name "PWM_MT3A") (class "Default")
      (node (ref "GBA_CONNECTOR") (pin "P$21") (pinfunction "D5_P$21") (pintype "bidirectional"))
      (node (ref "U3") (pin "21") (pinfunction "AIN1_21") (pintype "bidirectional"))
    )
    (net (code "40") (name "PWM_MT3B_SERVO3") (class "Default")
      (node (ref "GBA_CONNECTOR") (pin "P$20") (pinfunction "D4_P$20") (pintype "bidirectional"))
      (node (ref "SERVO3") (pin "3") (pinfunction "S_3") (pintype "passive"))
      (node (ref "U3") (pin "22") (pinfunction "AIN2_22") (pintype "bidirectional"))
    )
    (net (code "41") (name "PWM_MT4A_SERVO4") (class "Default")
      (node (ref "GBA_CONNECTOR") (pin "P$22") (pinfunction "D6_P$22") (pintype "bidirectional"))
      (node (ref "SERVO4") (pin "3") (pinfunction "S_3") (pintype "passive"))
      (node (ref "U3") (pin "17") (pinfunction "BIN1_17") (pintype "bidirectional"))
    )
    (net (code "42") (name "PWM_MT4B") (class "Default")
      (node (ref "GBA_CONNECTOR") (pin "P$23") (pinfunction "D7_P$23") (pintype "bidirectional"))
      (node (ref "U3") (pin "16") (pinfunction "BIN2_16") (pintype "bidirectional"))
    )
    (net (code "43") (name "PWM_MT5A") (class "Default")
      (node (ref "GBA_CONNECTOR") (pin "P$25") (pinfunction "D9_P$25") (pintype "bidirectional"))
      (node (ref "TB6621FNG") (pin "21") (pinfunction "AIN1_21") (pintype "bidirectional"))
    )
    (net (code "44") (name "PWM_MT5B_SERVO5") (class "Default")
      (node (ref "GBA_CONNECTOR") (pin "P$24") (pinfunction "D8_P$24") (pintype "bidirectional"))
      (node (ref "SERVO5") (pin "3") (pinfunction "S_3") (pintype "passive"))
      (node (ref "TB6621FNG") (pin "22") (pinfunction "AIN2_22") (pintype "bidirectional"))
    )
    (net (code "45") (name "PWM_MT6A_SERVO6") (class "Default")
      (node (ref "GBA_CONNECTOR") (pin "P$26") (pinfunction "D10_P$26") (pintype "bidirectional"))
      (node (ref "SERVO6") (pin "3") (pinfunction "S_3") (pintype "passive"))
      (node (ref "TB6621FNG") (pin "17") (pinfunction "BIN1_17") (pintype "bidirectional"))
    )
    (net (code "46") (name "PWM_MT6B") (class "Default")
      (node (ref "GBA_CONNECTOR") (pin "P$27") (pinfunction "D11_P$27") (pintype "bidirectional"))
      (node (ref "TB6621FNG") (pin "16") (pinfunction "BIN2_16") (pintype "bidirectional"))
    )
    (net (code "47") (name "SCL") (class "Default")
      (node (ref "FINGER1") (pin "4") (pinfunction "4_4") (pintype "bidirectional"))
      (node (ref "FINGER2") (pin "4") (pinfunction "4_4") (pintype "bidirectional"))
      (node (ref "FINGER3") (pin "4") (pinfunction "4_4") (pintype "bidirectional"))
      (node (ref "FINGER4") (pin "4") (pinfunction "4_4") (pintype "bidirectional"))
      (node (ref "FINGER5") (pin "4") (pinfunction "4_4") (pintype "bidirectional"))
      (node (ref "FINGER6") (pin "4") (pinfunction "4_4") (pintype "bidirectional"))
      (node (ref "FINGER7") (pin "4") (pinfunction "4_4") (pintype "bidirectional"))
      (node (ref "GBA_CONNECTOR") (pin "P$31") (pinfunction "I2C_SCL_P$31") (pintype "bidirectional"))
      (node (ref "INA219") (pin "5") (pinfunction "SCL_5") (pintype "bidirectional"))
      (node (ref "R5") (pin "2") (pinfunction "2_2") (pintype "passive"))
    )
    (net (code "48") (name "SDA") (class "Default")
      (node (ref "FINGER1") (pin "5") (pinfunction "5_5") (pintype "bidirectional"))
      (node (ref "FINGER2") (pin "5") (pinfunction "5_5") (pintype "bidirectional"))
      (node (ref "FINGER3") (pin "5") (pinfunction "5_5") (pintype "bidirectional"))
      (node (ref "FINGER4") (pin "5") (pinfunction "5_5") (pintype "bidirectional"))
      (node (ref "FINGER5") (pin "5") (pinfunction "5_5") (pintype "bidirectional"))
      (node (ref "FINGER6") (pin "5") (pinfunction "5_5") (pintype "bidirectional"))
      (node (ref "FINGER7") (pin "5") (pinfunction "5_5") (pintype "bidirectional"))
      (node (ref "GBA_CONNECTOR") (pin "P$30") (pinfunction "I2C_SDA_P$30") (pintype "bidirectional"))
      (node (ref "INA219") (pin "6") (pinfunction "SDA_6") (pintype "bidirectional"))
      (node (ref "R4") (pin "2") (pinfunction "2_2") (pintype "passive"))
    )
    (net (code "49") (name "SOK") (class "Default")
      (node (ref "GBA_CONNECTOR") (pin "P$5") (pinfunction "SOK_P$5") (pintype "bidirectional"))
      (node (ref "R6") (pin "2") (pinfunction "2_2") (pintype "passive"))
      (node (ref "R7") (pin "1") (pinfunction "1_1") (pintype "passive"))
    )
    (net (code "50") (name "VBAT") (class "Default")
      (node (ref "5.0V_REGULATOR") (pin "2") (pinfunction "VIN_2") (pintype "bidirectional"))
      (node (ref "C19") (pin "1") (pinfunction "P$1_1") (pintype "passive"))
      (node (ref "INA219") (pin "2") (pinfunction "VIN-_2") (pintype "bidirectional"))
      (node (ref "INA_BYPASS") (pin "1") (pinfunction "1_1") (pintype "passive"))
      (node (ref "R18") (pin "2") (pinfunction "2_2") (pintype "passive"))
      (node (ref "R20") (pin "1") (pinfunction "1_1") (pintype "passive"))
    )
    (net (code "51") (name "VLIPO") (class "Default")
      (node (ref "BATTERY") (pin "3") (pinfunction "S_3") (pintype "passive"))
      (node (ref "INA219") (pin "1") (pinfunction "VIN+_1") (pintype "bidirectional"))
      (node (ref "INA_BYPASS") (pin "2") (pinfunction "2_2") (pintype "passive"))
      (node (ref "R20") (pin "2") (pinfunction "2_2") (pintype "passive"))
    )
    (net (code "52") (name "unconnected-(3.3V_REGULATOR-NC_1-Pad8)") (class "Default")
      (node (ref "3.3V_REGULATOR") (pin "8") (pinfunction "NC_1_8") (pintype "bidirectional"))
    )
    (net (code "53") (name "unconnected-(3.3V_REGULATOR-NC_2-Pad11)") (class "Default")
      (node (ref "3.3V_REGULATOR") (pin "11") (pinfunction "NC_2_11") (pintype "bidirectional"))
    )
    (net (code "54") (name "unconnected-(3.3V_REGULATOR-NC_3-Pad12)") (class "Default")
      (node (ref "3.3V_REGULATOR") (pin "12") (pinfunction "NC_3_12") (pintype "bidirectional"))
    )
    (net (code "55") (name "unconnected-(3.3V_REGULATOR-PG-Pad10)") (class "Default")
      (node (ref "3.3V_REGULATOR") (pin "10") (pinfunction "PG_10") (pintype "bidirectional"))
    )
    (net (code "56") (name "unconnected-(3.3V_REGULATOR-SEQ-Pad9)") (class "Default")
      (node (ref "3.3V_REGULATOR") (pin "9") (pinfunction "SEQ_9") (pintype "bidirectional"))
    )
    (net (code "57") (name "unconnected-(5.0V_REGULATOR-NC_1-Pad8)") (class "Default")
      (node (ref "5.0V_REGULATOR") (pin "8") (pinfunction "NC_1_8") (pintype "bidirectional"))
    )
    (net (code "58") (name "unconnected-(5.0V_REGULATOR-NC_2-Pad11)") (class "Default")
      (node (ref "5.0V_REGULATOR") (pin "11") (pinfunction "NC_2_11") (pintype "bidirectional"))
    )
    (net (code "59") (name "unconnected-(5.0V_REGULATOR-NC_3-Pad12)") (class "Default")
      (node (ref "5.0V_REGULATOR") (pin "12") (pinfunction "NC_3_12") (pintype "bidirectional"))
    )
    (net (code "60") (name "unconnected-(5.0V_REGULATOR-SEQ-Pad9)") (class "Default")
      (node (ref "5.0V_REGULATOR") (pin "9") (pinfunction "SEQ_9") (pintype "bidirectional"))
    )
    (net (code "61") (name "unconnected-(BATTERYB-S-Pad2)") (class "Default")
      (node (ref "BATTERY") (pin "2") (pinfunction "S_2") (pintype "passive"))
    )
    (net (code "62") (name "unconnected-(SW1-O-PadA)") (class "Default")
      (node (ref "SW1") (pin "A") (pinfunction "O_A") (pintype "passive"))
    )
  )
)
